# Driver5.net
KiCad netlist of a schematic drawn in Altium Designer
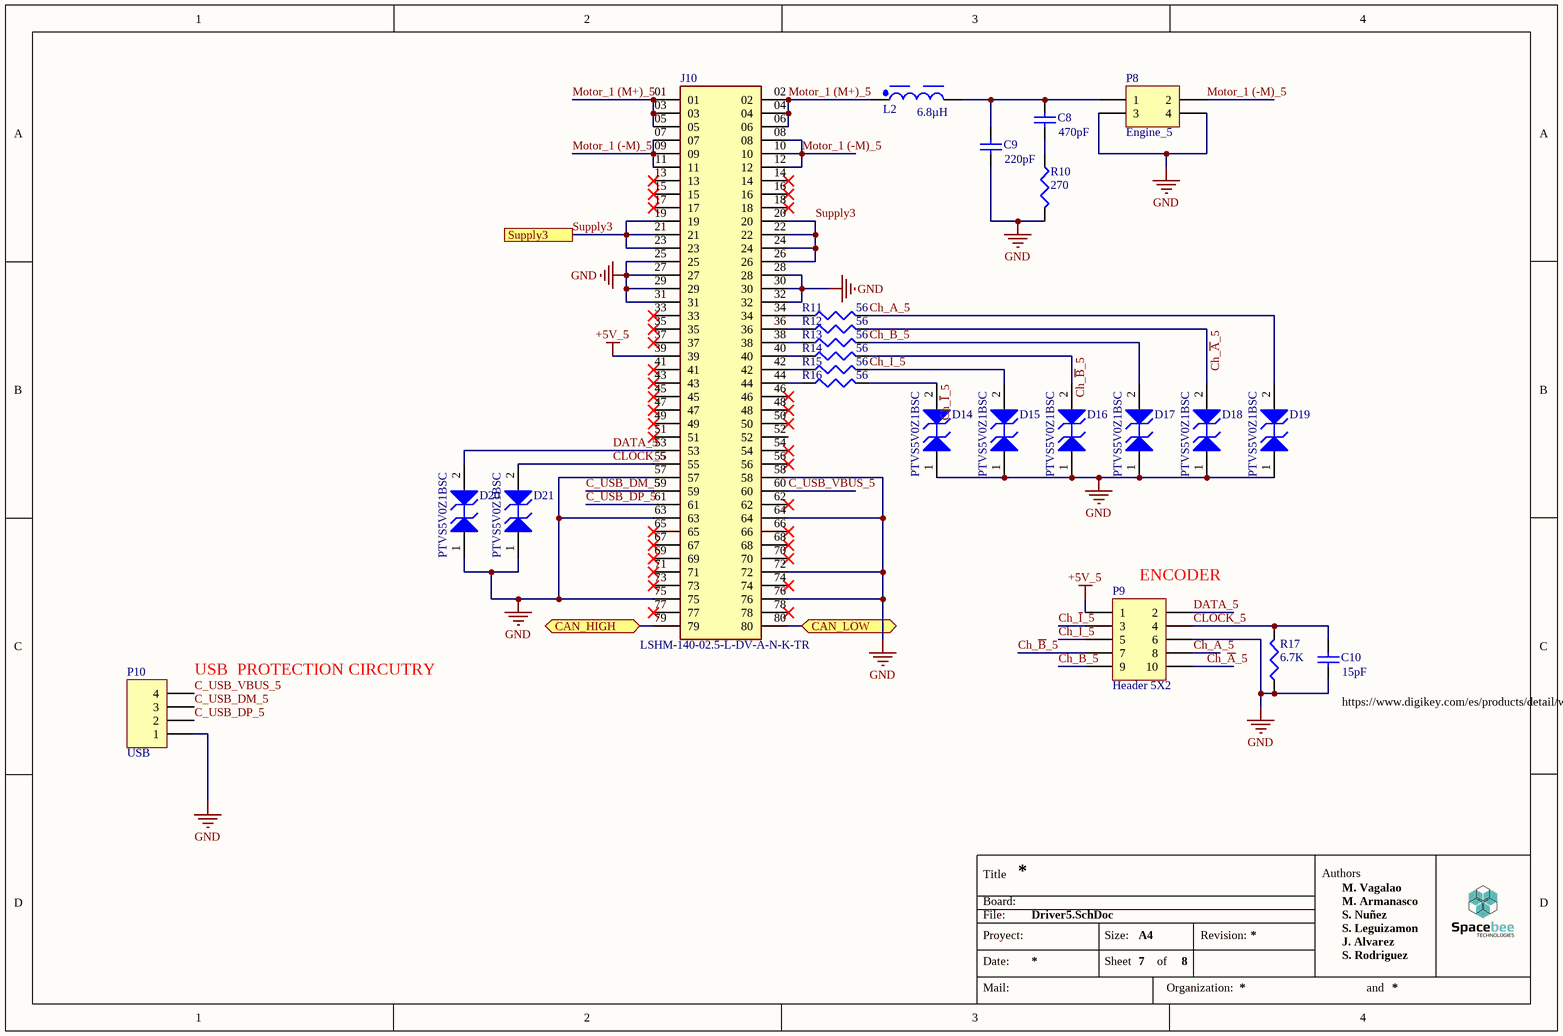
[diagram p0: Driver5.SchDoc]

(export (version "E")
  (design (tool "Eeschema 10.0.6"))
  (components
    (comp (ref "C8")
      (value "470pF")
      (footprint "1608[0603]")
      (description "Capacitor (Semiconductor SIM Model)")
      (fields (field (name "Comment") "Cap Semi") (field (name "PUBLISHER") "Altium Limited"))
      (libsource (lib "Miscellaneous Devices") (part "Cap Semi"))
    )
    (comp (ref "C9")
      (value "220pF")
      (footprint "1608[0603]")
      (description "Capacitor (Semiconductor SIM Model)")
      (fields (field (name "Comment") "Cap Semi") (field (name "PUBLISHER") "Altium Limited"))
      (libsource (lib "Miscellaneous Devices") (part "Cap Semi"))
    )
    (comp (ref "C10")
      (value "15pF")
      (footprint "1608[0603]")
      (description "Capacitor (Semiconductor SIM Model)")
      (fields (field (name "Comment") "Cap Semi") (field (name "PUBLISHER") "Altium Limited"))
      (libsource (lib "Miscellaneous Devices") (part "Cap Semi"))
    )
    (comp (ref "D14")
      (value "PTVS5V0Z1BSC")
      (footprint "SOD993B")
      (fields (field (name "MANUFACTURER") "On Semiconductor") (field (name "PARTNUMBER") "1SMB16CAT3"))
      (libsource (lib "DriverLib") (part "PTVS5V0Z1BSC"))
    )
    (comp (ref "D15")
      (value "PTVS5V0Z1BSC")
      (footprint "SOD993B")
      (fields (field (name "MANUFACTURER") "On Semiconductor") (field (name "PARTNUMBER") "1SMB16CAT3"))
      (libsource (lib "DriverLib") (part "PTVS5V0Z1BSC"))
    )
    (comp (ref "D16")
      (value "PTVS5V0Z1BSC")
      (footprint "SOD993B")
      (fields (field (name "MANUFACTURER") "On Semiconductor") (field (name "PARTNUMBER") "1SMB16CAT3"))
      (libsource (lib "DriverLib") (part "PTVS5V0Z1BSC"))
    )
    (comp (ref "D17")
      (value "PTVS5V0Z1BSC")
      (footprint "SOD993B")
      (fields (field (name "MANUFACTURER") "On Semiconductor") (field (name "PARTNUMBER") "1SMB16CAT3"))
      (libsource (lib "DriverLib") (part "PTVS5V0Z1BSC"))
    )
    (comp (ref "D18")
      (value "PTVS5V0Z1BSC")
      (footprint "SOD993B")
      (fields (field (name "MANUFACTURER") "On Semiconductor") (field (name "PARTNUMBER") "1SMB16CAT3"))
      (libsource (lib "DriverLib") (part "PTVS5V0Z1BSC"))
    )
    (comp (ref "D19")
      (value "PTVS5V0Z1BSC")
      (footprint "SOD993B")
      (fields (field (name "MANUFACTURER") "On Semiconductor") (field (name "PARTNUMBER") "1SMB16CAT3"))
      (libsource (lib "DriverLib") (part "PTVS5V0Z1BSC"))
    )
    (comp (ref "D20")
      (value "PTVS5V0Z1BSC")
      (footprint "SOD993B")
      (fields (field (name "MANUFACTURER") "On Semiconductor") (field (name "PARTNUMBER") "1SMB16CAT3"))
      (libsource (lib "DriverLib") (part "PTVS5V0Z1BSC"))
    )
    (comp (ref "D21")
      (value "PTVS5V0Z1BSC")
      (footprint "SOD993B")
      (fields (field (name "MANUFACTURER") "On Semiconductor") (field (name "PARTNUMBER") "1SMB16CAT3"))
      (libsource (lib "DriverLib") (part "PTVS5V0Z1BSC"))
    )
    (comp (ref "J10")
      (value "LSHM-140-02.5-L-DV-A-N-K-TR")
      (footprint "SAMTEC_LSHM-140-02.5-L-DV-A-N-K-TR")
      (description "LSHM - Samtec 0.50mm Razor Beam High-Speed Hermaphroditic Terminal / Socket Strip.")
      (libsource (lib "DriverLib") (part "LSHM-140-02.5-L-DV-A-N-K-TR"))
    )
    (comp (ref "L2")
      (value "6.8µH")
      (footprint "WE-XHMA_6060")
      (description "WE-XHMA SMD Power Inductor, size 1090, 6.8µH, 10.5A, 7.16mΩ")
      (fields
        (field (name "MANUFACTURER PART NUMBER") "78439369068")
        (field (name "MANUFACTURER") "Wurth Elektronik")
      )
      (libsource (lib "DriverLib") (part "78439369068"))
    )
    (comp (ref "P8")
      (value "Engine_5")
      (footprint "MOLEX_1724480004")
      (description "Header, 2-Pin, Dual row")
      (fields (field (name "PUBLISHER") "Altium Limited"))
      (libsource (lib "SpaceBee") (part "Header 2X2"))
    )
    (comp (ref "P9")
      (value "Header 5X2")
      (footprint "CONN_HIF3FC-14PA-2.54DS(71)_HIR")
      (description "Header, 5-Pin, Dual row")
      (fields (field (name "PUBLISHER") "Altium Limited"))
      (libsource (lib "DriverLib") (part "Header 5X2"))
    )
    (comp (ref "P10")
      (value "USB")
      (footprint "HDR1X4")
      (description "Header, 4-Pin")
      (fields (field (name "PUBLISHER") "Altium Limited"))
      (libsource (lib "Miscellaneous Connectors") (part "Header 4"))
    )
    (comp (ref "R10")
      (value "270")
      (footprint "J1-0603")
      (description "Resistor")
      (fields (field (name "Comment") "Res3") (field (name "PUBLISHER") "Altium Limited"))
      (libsource (lib "Miscellaneous Devices") (part "Res3"))
    )
    (comp (ref "R11")
      (value "56")
      (footprint "J1-0603")
      (description "Resistor")
      (fields (field (name "Comment") "Res3") (field (name "PUBLISHER") "Altium Limited"))
      (libsource (lib "Miscellaneous Devices") (part "Res3"))
    )
    (comp (ref "R12")
      (value "56")
      (footprint "J1-0603")
      (description "Resistor")
      (fields (field (name "Comment") "Res3") (field (name "PUBLISHER") "Altium Limited"))
      (libsource (lib "Miscellaneous Devices") (part "Res3"))
    )
    (comp (ref "R13")
      (value "56")
      (footprint "J1-0603")
      (description "Resistor")
      (fields (field (name "Comment") "Res3") (field (name "PUBLISHER") "Altium Limited"))
      (libsource (lib "Miscellaneous Devices") (part "Res3"))
    )
    (comp (ref "R14")
      (value "56")
      (footprint "J1-0603")
      (description "Resistor")
      (fields (field (name "Comment") "Res3") (field (name "PUBLISHER") "Altium Limited"))
      (libsource (lib "Miscellaneous Devices") (part "Res3"))
    )
    (comp (ref "R15")
      (value "56")
      (footprint "J1-0603")
      (description "Resistor")
      (fields (field (name "Comment") "Res3") (field (name "PUBLISHER") "Altium Limited"))
      (libsource (lib "Miscellaneous Devices") (part "Res3"))
    )
    (comp (ref "R16")
      (value "56")
      (footprint "J1-0603")
      (description "Resistor")
      (fields (field (name "Comment") "Res3") (field (name "PUBLISHER") "Altium Limited"))
      (libsource (lib "Miscellaneous Devices") (part "Res3"))
    )
    (comp (ref "R17")
      (value "6.7K")
      (footprint "J1-0603")
      (description "Resistor")
      (fields (field (name "Comment") "Res3") (field (name "PUBLISHER") "Altium Limited"))
      (libsource (lib "Miscellaneous Devices") (part "Res3"))
    )
  )
  (nets
    (net (code "1") (name "+5V_5") (class "Default")
      (node (ref "J10") (pin "39") (pinfunction "39_39") (pintype "passive"))
      (node (ref "P9") (pin "1") (pinfunction "1_1") (pintype "passive"))
    )
    (net (code "2") (name "/CAN_HIGH") (class "Default")
      (node (ref "J10") (pin "79") (pinfunction "79_79") (pintype "passive"))
    )
    (net (code "3") (name "/CAN_LOW") (class "Default")
      (node (ref "J10") (pin "80") (pinfunction "80_80") (pintype "passive"))
    )
    (net (code "4") (name "/CLOCK_5") (class "Default")
      (node (ref "C10") (pin "1") (pinfunction "1_1") (pintype "passive"))
      (node (ref "D21") (pin "2") (pinfunction "A2_2") (pintype "passive"))
      (node (ref "J10") (pin "55") (pinfunction "55_55") (pintype "passive"))
      (node (ref "P9") (pin "4") (pinfunction "4_4") (pintype "passive"))
      (node (ref "R17") (pin "2") (pinfunction "2_2") (pintype "passive"))
    )
    (net (code "5") (name "/C_USB_DM_5") (class "Default")
      (node (ref "J10") (pin "59") (pinfunction "59_59") (pintype "passive"))
      (node (ref "P10") (pin "3") (pinfunction "3_3") (pintype "passive"))
    )
    (net (code "6") (name "/C_USB_DP_5") (class "Default")
      (node (ref "J10") (pin "61") (pinfunction "61_61") (pintype "passive"))
      (node (ref "P10") (pin "2") (pinfunction "2_2") (pintype "passive"))
    )
    (net (code "7") (name "/C_USB_VBUS_5") (class "Default")
      (node (ref "J10") (pin "60") (pinfunction "60_60") (pintype "passive"))
      (node (ref "P10") (pin "4") (pinfunction "4_4") (pintype "passive"))
    )
    (net (code "8") (name "/Ch_A_5") (class "Default")
      (node (ref "D19") (pin "2") (pinfunction "A2_2") (pintype "passive"))
      (node (ref "P9") (pin "8") (pinfunction "8_8") (pintype "passive"))
      (node (ref "R11") (pin "2") (pinfunction "2_2") (pintype "passive"))
    )
    (net (code "9") (name "/Ch_B_5") (class "Default")
      (node (ref "D17") (pin "2") (pinfunction "A2_2") (pintype "passive"))
      (node (ref "P9") (pin "9") (pinfunction "9_9") (pintype "passive"))
      (node (ref "R13") (pin "2") (pinfunction "2_2") (pintype "passive"))
    )
    (net (code "10") (name "/Ch_I_5") (class "Default")
      (node (ref "D15") (pin "2") (pinfunction "A2_2") (pintype "passive"))
      (node (ref "P9") (pin "5") (pinfunction "5_5") (pintype "passive"))
      (node (ref "R15") (pin "2") (pinfunction "2_2") (pintype "passive"))
    )
    (net (code "11") (name "/Ch_~{A}_5") (class "Default")
      (node (ref "D18") (pin "2") (pinfunction "A2_2") (pintype "passive"))
      (node (ref "P9") (pin "10") (pinfunction "10_10") (pintype "passive"))
      (node (ref "R12") (pin "2") (pinfunction "2_2") (pintype "passive"))
    )
    (net (code "12") (name "/Ch_~{B}_5") (class "Default")
      (node (ref "D16") (pin "2") (pinfunction "A2_2") (pintype "passive"))
      (node (ref "P9") (pin "7") (pinfunction "7_7") (pintype "passive"))
      (node (ref "R14") (pin "2") (pinfunction "2_2") (pintype "passive"))
    )
    (net (code "13") (name "/Ch_~{I}_5") (class "Default")
      (node (ref "D14") (pin "2") (pinfunction "A2_2") (pintype "passive"))
      (node (ref "P9") (pin "3") (pinfunction "3_3") (pintype "passive"))
      (node (ref "R16") (pin "2") (pinfunction "2_2") (pintype "passive"))
    )
    (net (code "14") (name "/DATA_5") (class "Default")
      (node (ref "D20") (pin "2") (pinfunction "A2_2") (pintype "passive"))
      (node (ref "J10") (pin "53") (pinfunction "53_53") (pintype "passive"))
      (node (ref "P9") (pin "2") (pinfunction "2_2") (pintype "passive"))
    )
    (net (code "15") (name "/Motor_1 (-M)_5") (class "Default")
      (node (ref "J10") (pin "07") (pinfunction "07_07") (pintype "passive"))
      (node (ref "J10") (pin "08") (pinfunction "08_08") (pintype "passive"))
      (node (ref "J10") (pin "09") (pinfunction "09_09") (pintype "passive"))
      (node (ref "J10") (pin "10") (pinfunction "10_10") (pintype "passive"))
      (node (ref "J10") (pin "11") (pinfunction "11_11") (pintype "passive"))
      (node (ref "J10") (pin "12") (pinfunction "12_12") (pintype "passive"))
      (node (ref "P8") (pin "2") (pinfunction "2_2") (pintype "passive"))
    )
    (net (code "16") (name "/Motor_1 (M+)_5") (class "Default")
      (node (ref "J10") (pin "01") (pinfunction "01_01") (pintype "passive"))
      (node (ref "J10") (pin "02") (pinfunction "02_02") (pintype "passive"))
      (node (ref "J10") (pin "03") (pinfunction "03_03") (pintype "passive"))
      (node (ref "J10") (pin "04") (pinfunction "04_04") (pintype "passive"))
      (node (ref "J10") (pin "05") (pinfunction "05_05") (pintype "passive"))
      (node (ref "J10") (pin "06") (pinfunction "06_06") (pintype "passive"))
      (node (ref "L2") (pin "1") (pinfunction "1_1") (pintype "passive"))
    )
    (net (code "17") (name "/Supply3") (class "Default")
      (node (ref "J10") (pin "19") (pinfunction "19_19") (pintype "passive"))
      (node (ref "J10") (pin "20") (pinfunction "20_20") (pintype "passive"))
      (node (ref "J10") (pin "21") (pinfunction "21_21") (pintype "passive"))
      (node (ref "J10") (pin "22") (pinfunction "22_22") (pintype "passive"))
      (node (ref "J10") (pin "23") (pinfunction "23_23") (pintype "passive"))
      (node (ref "J10") (pin "24") (pinfunction "24_24") (pintype "passive"))
      (node (ref "J10") (pin "26") (pinfunction "26_26") (pintype "passive"))
    )
    (net (code "18") (name "GND") (class "Default")
      (node (ref "C10") (pin "2") (pinfunction "2_2") (pintype "passive"))
      (node (ref "C9") (pin "2") (pinfunction "2_2") (pintype "passive"))
      (node (ref "D14") (pin "1") (pinfunction "A1_1") (pintype "passive"))
      (node (ref "D15") (pin "1") (pinfunction "A1_1") (pintype "passive"))
      (node (ref "D16") (pin "1") (pinfunction "A1_1") (pintype "passive"))
      (node (ref "D17") (pin "1") (pinfunction "A1_1") (pintype "passive"))
      (node (ref "D18") (pin "1") (pinfunction "A1_1") (pintype "passive"))
      (node (ref "D19") (pin "1") (pinfunction "A1_1") (pintype "passive"))
      (node (ref "D20") (pin "1") (pinfunction "A1_1") (pintype "passive"))
      (node (ref "D21") (pin "1") (pinfunction "A1_1") (pintype "passive"))
      (node (ref "J10") (pin "25") (pinfunction "25_25") (pintype "passive"))
      (node (ref "J10") (pin "27") (pinfunction "27_27") (pintype "passive"))
      (node (ref "J10") (pin "28") (pinfunction "28_28") (pintype "passive"))
      (node (ref "J10") (pin "29") (pinfunction "29_29") (pintype "passive"))
      (node (ref "J10") (pin "30") (pinfunction "30_30") (pintype "passive"))
      (node (ref "J10") (pin "31") (pinfunction "31_31") (pintype "passive"))
      (node (ref "J10") (pin "32") (pinfunction "32_32") (pintype "passive"))
      (node (ref "J10") (pin "57") (pinfunction "57_57") (pintype "passive"))
      (node (ref "J10") (pin "58") (pinfunction "58_58") (pintype "passive"))
      (node (ref "J10") (pin "63") (pinfunction "63_63") (pintype "passive"))
      (node (ref "J10") (pin "64") (pinfunction "64_64") (pintype "passive"))
      (node (ref "J10") (pin "72") (pinfunction "72_72") (pintype "passive"))
      (node (ref "J10") (pin "75") (pinfunction "75_75") (pintype "passive"))
      (node (ref "J10") (pin "76") (pinfunction "76_76") (pintype "passive"))
      (node (ref "P10") (pin "1") (pinfunction "1_1") (pintype "passive"))
      (node (ref "P8") (pin "3") (pinfunction "3_3") (pintype "passive"))
      (node (ref "P8") (pin "4") (pinfunction "4_4") (pintype "passive"))
      (node (ref "P9") (pin "6") (pinfunction "6_6") (pintype "passive"))
      (node (ref "R10") (pin "2") (pinfunction "2_2") (pintype "passive"))
      (node (ref "R17") (pin "1") (pinfunction "1_1") (pintype "passive"))
    )
    (net (code "19") (name "Net-(C8-Pad1)") (class "Default")
      (node (ref "C8") (pin "1") (pinfunction "1_1") (pintype "passive"))
      (node (ref "C9") (pin "1") (pinfunction "1_1") (pintype "passive"))
      (node (ref "L2") (pin "2") (pinfunction "2_2") (pintype "passive"))
      (node (ref "P8") (pin "1") (pinfunction "1_1") (pintype "passive"))
    )
    (net (code "20") (name "Net-(C8-Pad2)") (class "Default")
      (node (ref "C8") (pin "2") (pinfunction "2_2") (pintype "passive"))
      (node (ref "R10") (pin "1") (pinfunction "1_1") (pintype "passive"))
    )
    (net (code "21") (name "Net-(J10-Pad34)") (class "Default")
      (node (ref "J10") (pin "34") (pinfunction "34_34") (pintype "passive"))
      (node (ref "R11") (pin "1") (pinfunction "1_1") (pintype "passive"))
    )
    (net (code "22") (name "Net-(J10-Pad36)") (class "Default")
      (node (ref "J10") (pin "36") (pinfunction "36_36") (pintype "passive"))
      (node (ref "R12") (pin "1") (pinfunction "1_1") (pintype "passive"))
    )
    (net (code "23") (name "Net-(J10-Pad38)") (class "Default")
      (node (ref "J10") (pin "38") (pinfunction "38_38") (pintype "passive"))
      (node (ref "R13") (pin "1") (pinfunction "1_1") (pintype "passive"))
    )
    (net (code "24") (name "Net-(J10-Pad40)") (class "Default")
      (node (ref "J10") (pin "40") (pinfunction "40_40") (pintype "passive"))
      (node (ref "R14") (pin "1") (pinfunction "1_1") (pintype "passive"))
    )
    (net (code "25") (name "Net-(J10-Pad42)") (class "Default")
      (node (ref "J10") (pin "42") (pinfunction "42_42") (pintype "passive"))
      (node (ref "R15") (pin "1") (pinfunction "1_1") (pintype "passive"))
    )
    (net (code "26") (name "Net-(J10-Pad44)") (class "Default")
      (node (ref "J10") (pin "44") (pinfunction "44_44") (pintype "passive"))
      (node (ref "R16") (pin "1") (pinfunction "1_1") (pintype "passive"))
    )
    (net (code "27") (name "unconnected-(J10-Pad13)") (class "Default")
      (node (ref "J10") (pin "13") (pinfunction "13_13") (pintype "passive+no_connect"))
    )
    (net (code "28") (name "unconnected-(J10-Pad14)") (class "Default")
      (node (ref "J10") (pin "14") (pinfunction "14_14") (pintype "passive+no_connect"))
    )
    (net (code "29") (name "unconnected-(J10-Pad15)") (class "Default")
      (node (ref "J10") (pin "15") (pinfunction "15_15") (pintype "passive+no_connect"))
    )
    (net (code "30") (name "unconnected-(J10-Pad16)") (class "Default")
      (node (ref "J10") (pin "16") (pinfunction "16_16") (pintype "passive+no_connect"))
    )
    (net (code "31") (name "unconnected-(J10-Pad17)") (class "Default")
      (node (ref "J10") (pin "17") (pinfunction "17_17") (pintype "passive+no_connect"))
    )
    (net (code "32") (name "unconnected-(J10-Pad18)") (class "Default")
      (node (ref "J10") (pin "18") (pinfunction "18_18") (pintype "passive+no_connect"))
    )
    (net (code "33") (name "unconnected-(J10-Pad33)") (class "Default")
      (node (ref "J10") (pin "33") (pinfunction "33_33") (pintype "passive+no_connect"))
    )
    (net (code "34") (name "unconnected-(J10-Pad35)") (class "Default")
      (node (ref "J10") (pin "35") (pinfunction "35_35") (pintype "passive+no_connect"))
    )
    (net (code "35") (name "unconnected-(J10-Pad37)") (class "Default")
      (node (ref "J10") (pin "37") (pinfunction "37_37") (pintype "passive+no_connect"))
    )
    (net (code "36") (name "unconnected-(J10-Pad41)") (class "Default")
      (node (ref "J10") (pin "41") (pinfunction "41_41") (pintype "passive+no_connect"))
    )
    (net (code "37") (name "unconnected-(J10-Pad43)") (class "Default")
      (node (ref "J10") (pin "43") (pinfunction "43_43") (pintype "passive+no_connect"))
    )
    (net (code "38") (name "unconnected-(J10-Pad45)") (class "Default")
      (node (ref "J10") (pin "45") (pinfunction "45_45") (pintype "passive+no_connect"))
    )
    (net (code "39") (name "unconnected-(J10-Pad46)") (class "Default")
      (node (ref "J10") (pin "46") (pinfunction "46_46") (pintype "passive+no_connect"))
    )
    (net (code "40") (name "unconnected-(J10-Pad47)") (class "Default")
      (node (ref "J10") (pin "47") (pinfunction "47_47") (pintype "passive+no_connect"))
    )
    (net (code "41") (name "unconnected-(J10-Pad48)") (class "Default")
      (node (ref "J10") (pin "48") (pinfunction "48_48") (pintype "passive+no_connect"))
    )
    (net (code "42") (name "unconnected-(J10-Pad49)") (class "Default")
      (node (ref "J10") (pin "49") (pinfunction "49_49") (pintype "passive+no_connect"))
    )
    (net (code "43") (name "unconnected-(J10-Pad50)") (class "Default")
      (node (ref "J10") (pin "50") (pinfunction "50_50") (pintype "passive+no_connect"))
    )
    (net (code "44") (name "unconnected-(J10-Pad51)") (class "Default")
      (node (ref "J10") (pin "51") (pinfunction "51_51") (pintype "passive+no_connect"))
    )
    (net (code "45") (name "unconnected-(J10-Pad52)") (class "Default")
      (node (ref "J10") (pin "52") (pinfunction "52_52") (pintype "passive"))
    )
    (net (code "46") (name "unconnected-(J10-Pad54)") (class "Default")
      (node (ref "J10") (pin "54") (pinfunction "54_54") (pintype "passive+no_connect"))
    )
    (net (code "47") (name "unconnected-(J10-Pad56)") (class "Default")
      (node (ref "J10") (pin "56") (pinfunction "56_56") (pintype "passive+no_connect"))
    )
    (net (code "48") (name "unconnected-(J10-Pad62)") (class "Default")
      (node (ref "J10") (pin "62") (pinfunction "62_62") (pintype "passive+no_connect"))
    )
    (net (code "49") (name "unconnected-(J10-Pad65)") (class "Default")
      (node (ref "J10") (pin "65") (pinfunction "65_65") (pintype "passive+no_connect"))
    )
    (net (code "50") (name "unconnected-(J10-Pad66)") (class "Default")
      (node (ref "J10") (pin "66") (pinfunction "66_66") (pintype "passive+no_connect"))
    )
    (net (code "51") (name "unconnected-(J10-Pad67)") (class "Default")
      (node (ref "J10") (pin "67") (pinfunction "67_67") (pintype "passive+no_connect"))
    )
    (net (code "52") (name "unconnected-(J10-Pad68)") (class "Default")
      (node (ref "J10") (pin "68") (pinfunction "68_68") (pintype "passive+no_connect"))
    )
    (net (code "53") (name "unconnected-(J10-Pad69)") (class "Default")
      (node (ref "J10") (pin "69") (pinfunction "69_69") (pintype "passive+no_connect"))
    )
    (net (code "54") (name "unconnected-(J10-Pad70)") (class "Default")
      (node (ref "J10") (pin "70") (pinfunction "70_70") (pintype "passive+no_connect"))
    )
    (net (code "55") (name "unconnected-(J10-Pad71)") (class "Default")
      (node (ref "J10") (pin "71") (pinfunction "71_71") (pintype "passive+no_connect"))
    )
    (net (code "56") (name "unconnected-(J10-Pad73)") (class "Default")
      (node (ref "J10") (pin "73") (pinfunction "73_73") (pintype "passive+no_connect"))
    )
    (net (code "57") (name "unconnected-(J10-Pad74)") (class "Default")
      (node (ref "J10") (pin "74") (pinfunction "74_74") (pintype "passive+no_connect"))
    )
    (net (code "58") (name "unconnected-(J10-Pad77)") (class "Default")
      (node (ref "J10") (pin "77") (pinfunction "77_77") (pintype "passive+no_connect"))
    )
    (net (code "59") (name "unconnected-(J10-Pad78)") (class "Default")
      (node (ref "J10") (pin "78") (pinfunction "78_78") (pintype "passive+no_connect"))
    )
  )
)
